# Bluesaab_RN52_v5_5-DPAK.net
KiCad netlist of a schematic drawn in EAGLE
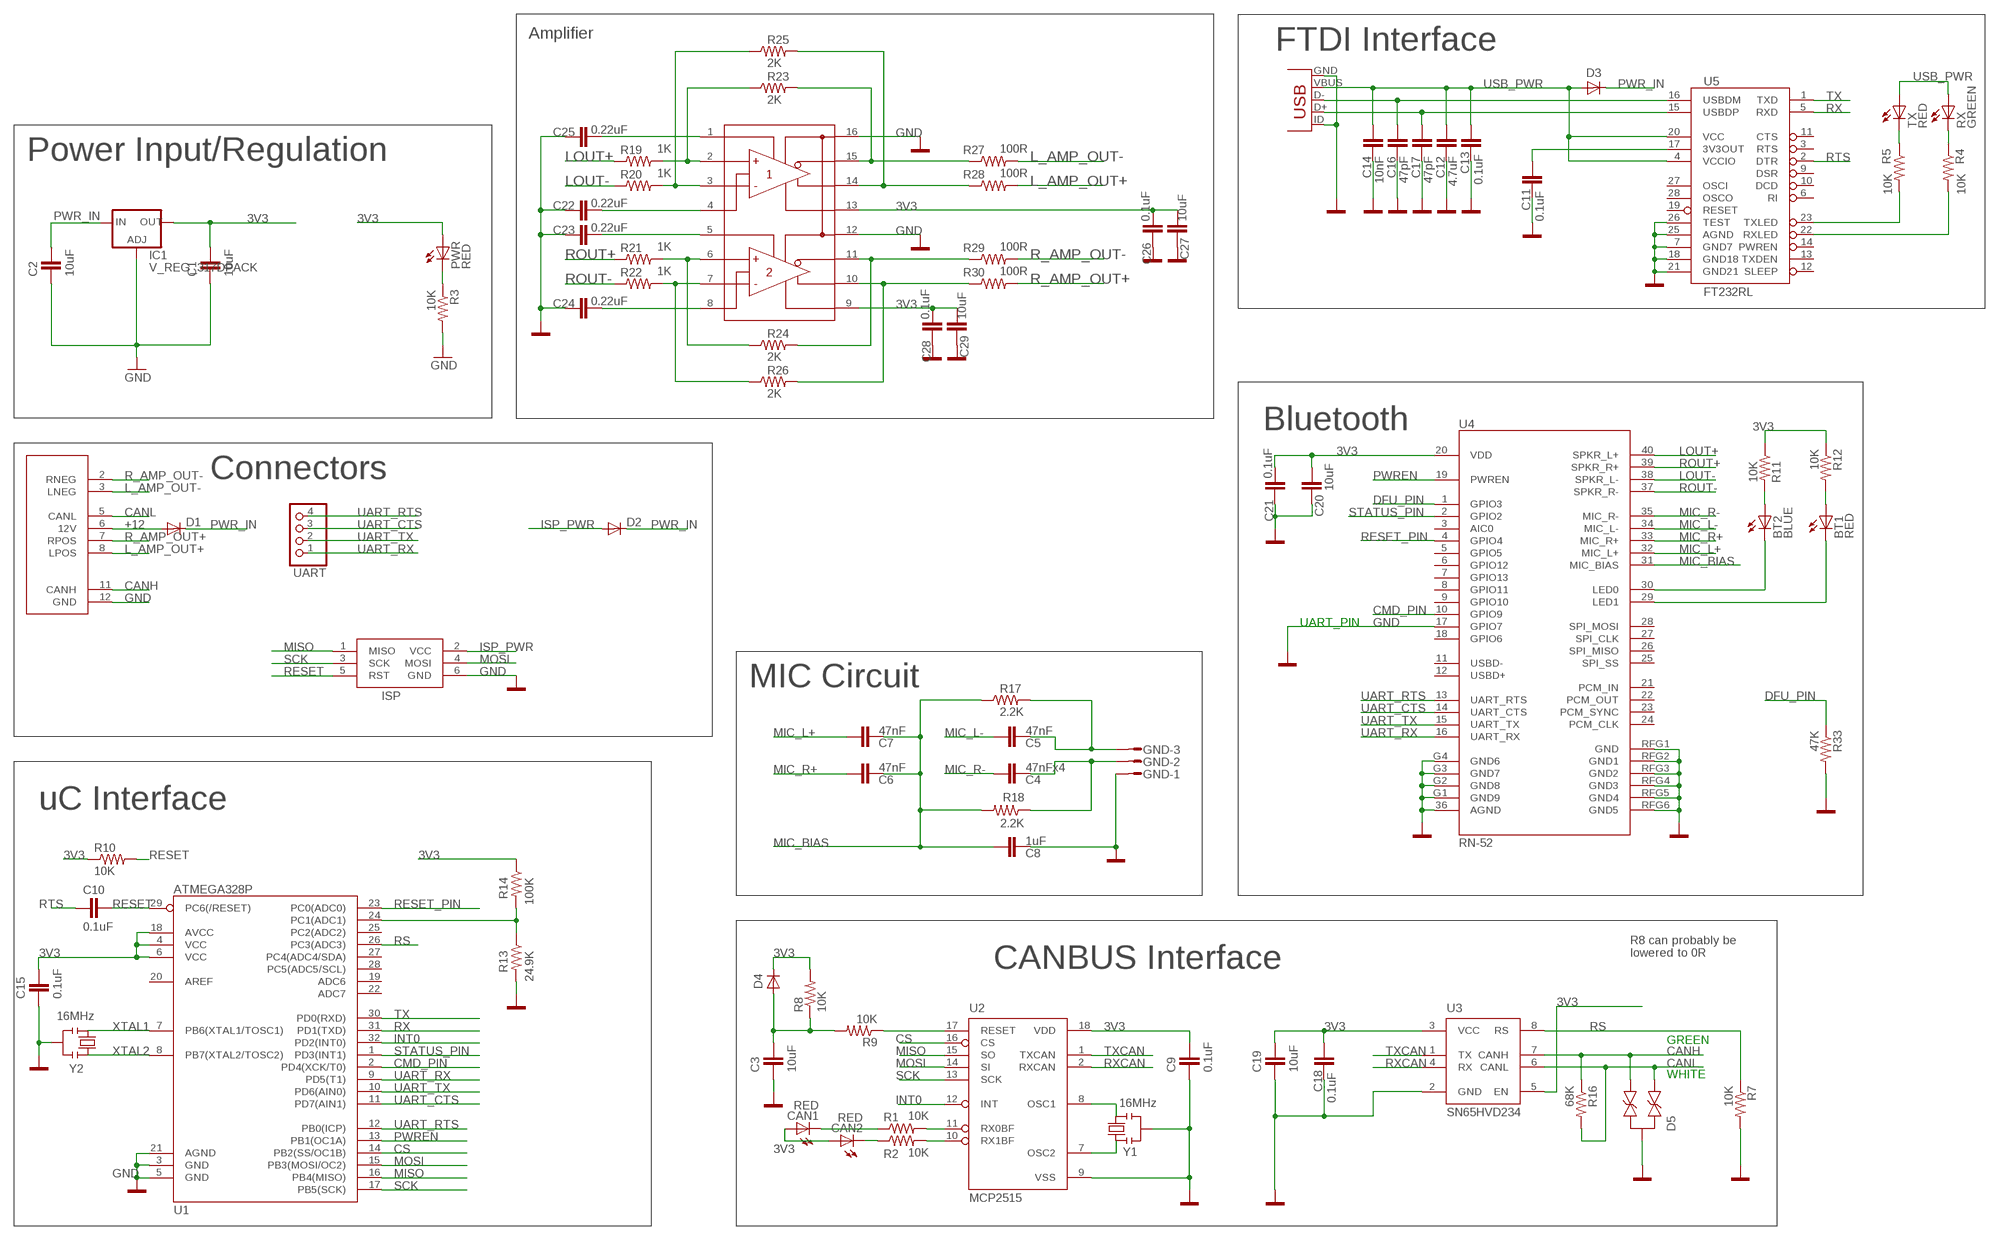
[diagram p0: schematic, sheet 1]

(export (version "E")
  (design (tool "Eeschema 10.0.6"))
  (components
    (comp (ref "BT1")
      (value "RED")
      (footprint "eagle-import:CHIPLED_0805")
      (libsource (lib "eagle-import") (part "LEDCHIPLED_0805"))
    )
    (comp (ref "BT2")
      (value "BLUE")
      (footprint "eagle-import:CHIPLED_0805")
      (libsource (lib "eagle-import") (part "LEDCHIPLED_0805"))
    )
    (comp (ref "C1")
      (value "10uF")
      (footprint "eagle-import:C0805K")
      (libsource (lib "eagle-import") (part "C-EUC0805K"))
    )
    (comp (ref "C2")
      (value "10uF")
      (footprint "eagle-import:C0805K")
      (libsource (lib "eagle-import") (part "C-EUC0805K"))
    )
    (comp (ref "C3")
      (value "10uF")
      (footprint "eagle-import:C0805K")
      (libsource (lib "eagle-import") (part "C-EUC0805K"))
    )
    (comp (ref "C4")
      (value "47nFx4")
      (footprint "eagle-import:C0805K")
      (libsource (lib "eagle-import") (part "C-EUC0805K"))
    )
    (comp (ref "C5")
      (value "47nF")
      (footprint "eagle-import:C0805K")
      (libsource (lib "eagle-import") (part "C-EUC0805K"))
    )
    (comp (ref "C6")
      (value "47nF")
      (footprint "eagle-import:C0805K")
      (libsource (lib "eagle-import") (part "C-EUC0805K"))
    )
    (comp (ref "C7")
      (value "47nF")
      (footprint "eagle-import:C0805K")
      (libsource (lib "eagle-import") (part "C-EUC0805K"))
    )
    (comp (ref "C8")
      (value "1uF")
      (footprint "eagle-import:C0805K")
      (libsource (lib "eagle-import") (part "C-EUC0805K"))
    )
    (comp (ref "C9")
      (value "0.1uF")
      (footprint "eagle-import:C0805K")
      (libsource (lib "eagle-import") (part "C-EUC0805K"))
    )
    (comp (ref "C10")
      (value "0.1uF")
      (footprint "eagle-import:C0805K")
      (libsource (lib "eagle-import") (part "C-EUC0805K"))
    )
    (comp (ref "C11")
      (value "0.1uF")
      (footprint "eagle-import:C0805K")
      (libsource (lib "eagle-import") (part "C-EUC0805K"))
    )
    (comp (ref "C12")
      (value "4.7uF")
      (footprint "eagle-import:C0805K")
      (libsource (lib "eagle-import") (part "C-EUC0805K"))
    )
    (comp (ref "C13")
      (value "0.1uF")
      (footprint "eagle-import:C0805K")
      (libsource (lib "eagle-import") (part "C-EUC0805K"))
    )
    (comp (ref "C14")
      (value "10nF")
      (footprint "eagle-import:C0805K")
      (libsource (lib "eagle-import") (part "C-EUC0805K"))
    )
    (comp (ref "C15")
      (value "0.1uF")
      (footprint "eagle-import:C0805K")
      (libsource (lib "eagle-import") (part "C-EUC0805K"))
    )
    (comp (ref "C16")
      (value "47pF")
      (footprint "eagle-import:C0805K")
      (libsource (lib "eagle-import") (part "C-EUC0805K"))
    )
    (comp (ref "C17")
      (value "47pF")
      (footprint "eagle-import:C0805K")
      (libsource (lib "eagle-import") (part "C-EUC0805K"))
    )
    (comp (ref "C18")
      (value "0.1uF")
      (footprint "eagle-import:C0805K")
      (libsource (lib "eagle-import") (part "C-EUC0805K"))
    )
    (comp (ref "C19")
      (value "10uF")
      (footprint "eagle-import:C0805K")
      (libsource (lib "eagle-import") (part "C-EUC0805K"))
    )
    (comp (ref "C20")
      (value "10uF")
      (footprint "eagle-import:C0805K")
      (libsource (lib "eagle-import") (part "C-EUC0805K"))
    )
    (comp (ref "C21")
      (value "0.1uF")
      (footprint "eagle-import:C0805K")
      (libsource (lib "eagle-import") (part "C-EUC0805K"))
    )
    (comp (ref "C22")
      (value "0.22uF")
      (footprint "eagle-import:C0805K")
      (libsource (lib "eagle-import") (part "C-EUC0805K"))
    )
    (comp (ref "C23")
      (value "0.22uF")
      (footprint "eagle-import:C0805K")
      (libsource (lib "eagle-import") (part "C-EUC0805K"))
    )
    (comp (ref "C24")
      (value "0.22uF")
      (footprint "eagle-import:C0805K")
      (libsource (lib "eagle-import") (part "C-EUC0805K"))
    )
    (comp (ref "C25")
      (value "0.22uF")
      (footprint "eagle-import:C0805K")
      (libsource (lib "eagle-import") (part "C-EUC0805K"))
    )
    (comp (ref "C26")
      (value "0.1uF")
      (footprint "eagle-import:C0805K")
      (libsource (lib "eagle-import") (part "C-EUC0805K"))
    )
    (comp (ref "C27")
      (value "10uF")
      (footprint "eagle-import:C0805K")
      (libsource (lib "eagle-import") (part "C-EUC0805K"))
    )
    (comp (ref "C28")
      (value "0.1uF")
      (footprint "eagle-import:C0805K")
      (libsource (lib "eagle-import") (part "C-EUC0805K"))
    )
    (comp (ref "C29")
      (value "10uF")
      (footprint "eagle-import:C0805K")
      (libsource (lib "eagle-import") (part "C-EUC0805K"))
    )
    (comp (ref "CAN1")
      (value "RED")
      (footprint "eagle-import:CHIPLED_0805")
      (libsource (lib "eagle-import") (part "LEDCHIPLED_0805"))
    )
    (comp (ref "CAN2")
      (value "RED")
      (footprint "eagle-import:CHIPLED_0805")
      (libsource (lib "eagle-import") (part "LEDCHIPLED_0805"))
    )
    (comp (ref "CDC_CONNECTOR")
      (value "827229-1")
      (footprint "eagle-import:827229-1")
      (libsource (lib "eagle-import") (part "827229-1"))
    )
    (comp (ref "D1")
      (value "DIODE-SCHOTTKY_")
      (footprint "eagle-import:SOD123")
      (libsource (lib "eagle-import") (part "DIODE-SOD123"))
    )
    (comp (ref "D2")
      (value "DIODE-SCHOTTKY_")
      (footprint "eagle-import:SOD123")
      (libsource (lib "eagle-import") (part "DIODE-SOD123"))
    )
    (comp (ref "D3")
      (value "DIODE-SCHOTTKY_")
      (footprint "eagle-import:SOD123")
      (libsource (lib "eagle-import") (part "DIODE-SOD123"))
    )
    (comp (ref "D4")
      (value "DIODE-SCHOTTKY_")
      (footprint "eagle-import:SOD123")
      (libsource (lib "eagle-import") (part "DIODE-SOD123"))
    )
    (comp (ref "D5")
      (value "DIODE-ARRAY")
      (footprint "eagle-import:SOT23")
      (libsource (lib "eagle-import") (part "DIODE-ARRAY"))
    )
    (comp (ref "GND")
      (value "S03P")
      (footprint "eagle-import:S03P")
      (libsource (lib "eagle-import") (part "S03P"))
    )
    (comp (ref "IC1")
      (value "V_REG_317DPACK")
      (footprint "eagle-import:V-REG_DPACK")
      (libsource (lib "eagle-import") (part "V_REG_317DPACK"))
    )
    (comp (ref "ISP")
      (value "AVRISP-6")
      (footprint "eagle-import:AVRISP")
      (libsource (lib "eagle-import") (part "AVRISP-6"))
    )
    (comp (ref "PWR")
      (value "RED")
      (footprint "eagle-import:CHIPLED_0805")
      (libsource (lib "eagle-import") (part "LEDCHIPLED_0805"))
    )
    (comp (ref "R1")
      (value "10K")
      (footprint "eagle-import:R0805")
      (libsource (lib "eagle-import") (part "R-US_R0805"))
    )
    (comp (ref "R2")
      (value "10K")
      (footprint "eagle-import:R0805")
      (libsource (lib "eagle-import") (part "R-US_R0805"))
    )
    (comp (ref "R3")
      (value "10K")
      (footprint "eagle-import:R0805")
      (libsource (lib "eagle-import") (part "R-US_R0805"))
    )
    (comp (ref "R4")
      (value "10K")
      (footprint "eagle-import:R0805")
      (libsource (lib "eagle-import") (part "R-US_R0805"))
    )
    (comp (ref "R5")
      (value "10K")
      (footprint "eagle-import:R0805")
      (libsource (lib "eagle-import") (part "R-US_R0805"))
    )
    (comp (ref "R7")
      (value "10K")
      (footprint "eagle-import:R0805")
      (libsource (lib "eagle-import") (part "R-US_R0805"))
    )
    (comp (ref "R8")
      (value "10K")
      (footprint "eagle-import:R0805")
      (libsource (lib "eagle-import") (part "R-US_R0805"))
    )
    (comp (ref "R9")
      (value "10K")
      (footprint "eagle-import:R0805")
      (libsource (lib "eagle-import") (part "R-US_R0805"))
    )
    (comp (ref "R10")
      (value "10K")
      (footprint "eagle-import:R0805")
      (libsource (lib "eagle-import") (part "R-US_R0805"))
    )
    (comp (ref "R11")
      (value "10K")
      (footprint "eagle-import:R0805")
      (libsource (lib "eagle-import") (part "R-US_R0805"))
    )
    (comp (ref "R12")
      (value "10K")
      (footprint "eagle-import:R0805")
      (libsource (lib "eagle-import") (part "R-US_R0805"))
    )
    (comp (ref "R13")
      (value "24.9K")
      (footprint "eagle-import:R0805")
      (libsource (lib "eagle-import") (part "R-US_R0805"))
    )
    (comp (ref "R14")
      (value "100K")
      (footprint "eagle-import:R0805")
      (libsource (lib "eagle-import") (part "R-US_R0805"))
    )
    (comp (ref "R16")
      (value "68K")
      (footprint "eagle-import:R0805")
      (libsource (lib "eagle-import") (part "R-US_R0805"))
    )
    (comp (ref "R17")
      (value "2.2K")
      (footprint "eagle-import:R0805")
      (libsource (lib "eagle-import") (part "R-US_R0805"))
    )
    (comp (ref "R18")
      (value "2.2K")
      (footprint "eagle-import:R0805")
      (libsource (lib "eagle-import") (part "R-US_R0805"))
    )
    (comp (ref "R19")
      (value "1K")
      (footprint "eagle-import:R0805")
      (libsource (lib "eagle-import") (part "R-US_R0805"))
    )
    (comp (ref "R20")
      (value "1K")
      (footprint "eagle-import:R0805")
      (libsource (lib "eagle-import") (part "R-US_R0805"))
    )
    (comp (ref "R21")
      (value "1K")
      (footprint "eagle-import:R0805")
      (libsource (lib "eagle-import") (part "R-US_R0805"))
    )
    (comp (ref "R22")
      (value "1K")
      (footprint "eagle-import:R0805")
      (libsource (lib "eagle-import") (part "R-US_R0805"))
    )
    (comp (ref "R23")
      (value "2K")
      (footprint "eagle-import:R0805")
      (libsource (lib "eagle-import") (part "R-US_R0805"))
    )
    (comp (ref "R24")
      (value "2K")
      (footprint "eagle-import:R0805")
      (libsource (lib "eagle-import") (part "R-US_R0805"))
    )
    (comp (ref "R25")
      (value "2K")
      (footprint "eagle-import:R0805")
      (libsource (lib "eagle-import") (part "R-US_R0805"))
    )
    (comp (ref "R26")
      (value "2K")
      (footprint "eagle-import:R0805")
      (libsource (lib "eagle-import") (part "R-US_R0805"))
    )
    (comp (ref "R27")
      (value "100R")
      (footprint "eagle-import:R0805")
      (libsource (lib "eagle-import") (part "R-US_R0805"))
    )
    (comp (ref "R28")
      (value "100R")
      (footprint "eagle-import:R0805")
      (libsource (lib "eagle-import") (part "R-US_R0805"))
    )
    (comp (ref "R29")
      (value "100R")
      (footprint "eagle-import:R0805")
      (libsource (lib "eagle-import") (part "R-US_R0805"))
    )
    (comp (ref "R30")
      (value "100R")
      (footprint "eagle-import:R0805")
      (libsource (lib "eagle-import") (part "R-US_R0805"))
    )
    (comp (ref "R33")
      (value "47K")
      (footprint "eagle-import:R0805")
      (libsource (lib "eagle-import") (part "R-US_R0805"))
    )
    (comp (ref "RX")
      (value "GREEN")
      (footprint "eagle-import:CHIPLED_0805")
      (libsource (lib "eagle-import") (part "LEDCHIPLED_0805"))
    )
    (comp (ref "TX")
      (value "RED")
      (footprint "eagle-import:CHIPLED_0805")
      (libsource (lib "eagle-import") (part "LEDCHIPLED_0805"))
    )
    (comp (ref "U1")
      (value "ATMEGA328P")
      (footprint "eagle-import:TQFP32-08")
      (libsource (lib "eagle-import") (part "ATMEGA328_SMT"))
    )
    (comp (ref "U2")
      (value "MCP2515")
      (footprint "eagle-import:SO18L")
      (libsource (lib "eagle-import") (part "MCP2515"))
    )
    (comp (ref "U3")
      (value "SN65HVD234")
      (footprint "eagle-import:SO8")
      (libsource (lib "eagle-import") (part "SN65HVD234"))
    )
    (comp (ref "U4")
      (value "RN-52")
      (footprint "eagle-import:RN-52")
      (libsource (lib "eagle-import") (part "BLUETOOTH-RN-52"))
    )
    (comp (ref "U5")
      (value "FT232RL")
      (footprint "eagle-import:SSOP28DB")
      (libsource (lib "eagle-import") (part "FT232RLSSOP"))
    )
    (comp (ref "U7")
      (value "THS4522")
      (footprint "eagle-import:TSSOP-16")
      (libsource (lib "eagle-import") (part "THS4522"))
    )
    (comp (ref "UART")
      (value "PINHD-1X4")
      (footprint "eagle-import:1X04")
      (libsource (lib "eagle-import") (part "PINHD-1X4"))
    )
    (comp (ref "UPLOAD")
      (value "USB-MB-H")
      (footprint "eagle-import:USB-MB-H")
      (libsource (lib "eagle-import") (part "USB-MB-H"))
    )
    (comp (ref "Y1")
      (value "16MHz")
      (footprint "eagle-import:RESONATOR-SMD")
      (libsource (lib "eagle-import") (part "RESONATORSMD"))
    )
    (comp (ref "Y2")
      (value "16MHz")
      (footprint "eagle-import:RESONATOR-SMD")
      (libsource (lib "eagle-import") (part "RESONATORSMD"))
    )
  )
  (nets
    (net (code "1") (name "/+12") (class "Default")
      (node (ref "CDC_CONNECTOR") (pin "6") (pinfunction "12V_6") (pintype "bidirectional"))
      (node (ref "D1") (pin "A") (pinfunction "A_A") (pintype "passive"))
    )
    (net (code "2") (name "/3V3") (class "Default")
      (node (ref "C1") (pin "2") (pinfunction "2_2") (pintype "passive"))
      (node (ref "C15") (pin "2") (pinfunction "2_2") (pintype "passive"))
      (node (ref "C18") (pin "1") (pinfunction "1_1") (pintype "passive"))
      (node (ref "C19") (pin "2") (pinfunction "2_2") (pintype "passive"))
      (node (ref "C20") (pin "1") (pinfunction "1_1") (pintype "passive"))
      (node (ref "C21") (pin "2") (pinfunction "2_2") (pintype "passive"))
      (node (ref "C26") (pin "2") (pinfunction "2_2") (pintype "passive"))
      (node (ref "C27") (pin "1") (pinfunction "1_1") (pintype "passive"))
      (node (ref "C28") (pin "2") (pinfunction "2_2") (pintype "passive"))
      (node (ref "C29") (pin "1") (pinfunction "1_1") (pintype "passive"))
      (node (ref "C9") (pin "2") (pinfunction "2_2") (pintype "passive"))
      (node (ref "CAN1") (pin "A") (pinfunction "A_A") (pintype "passive"))
      (node (ref "CAN2") (pin "A") (pinfunction "A_A") (pintype "passive"))
      (node (ref "D4") (pin "C") (pinfunction "C_C") (pintype "passive"))
      (node (ref "IC1") (pin "4") (pinfunction "OUT_4") (pintype "output"))
      (node (ref "PWR") (pin "A") (pinfunction "A_A") (pintype "passive"))
      (node (ref "R10") (pin "1") (pinfunction "1_1") (pintype "passive"))
      (node (ref "R11") (pin "1") (pinfunction "1_1") (pintype "passive"))
      (node (ref "R12") (pin "1") (pinfunction "1_1") (pintype "passive"))
      (node (ref "R14") (pin "1") (pinfunction "1_1") (pintype "passive"))
      (node (ref "R8") (pin "2") (pinfunction "2_2") (pintype "passive"))
      (node (ref "U1") (pin "18") (pinfunction "AVCC_18") (pintype "bidirectional"))
      (node (ref "U1") (pin "4") (pinfunction "VCC_4") (pintype "bidirectional"))
      (node (ref "U1") (pin "6") (pinfunction "VCC_6") (pintype "bidirectional"))
      (node (ref "U2") (pin "18") (pinfunction "VDD_18") (pintype "power_in"))
      (node (ref "U3") (pin "3") (pinfunction "VCC_3") (pintype "power_in"))
      (node (ref "U3") (pin "5") (pinfunction "EN_5") (pintype "bidirectional"))
      (node (ref "U4") (pin "20") (pinfunction "VDD_20") (pintype "bidirectional"))
      (node (ref "U7") (pin "13") (pinfunction "13.VS+1_13") (pintype "power_in"))
      (node (ref "U7") (pin "9") (pinfunction "9.VS+2_9") (pintype "power_in"))
    )
    (net (code "3") (name "/CANH") (class "Default")
      (node (ref "CDC_CONNECTOR") (pin "11") (pinfunction "CANH_11") (pintype "bidirectional"))
      (node (ref "D5") (pin "2") (pinfunction "2_2") (pintype "bidirectional"))
      (node (ref "R16") (pin "1") (pinfunction "1_1") (pintype "passive"))
      (node (ref "U3") (pin "7") (pinfunction "CANH_7") (pintype "bidirectional"))
    )
    (net (code "4") (name "/CANL") (class "Default")
      (node (ref "CDC_CONNECTOR") (pin "5") (pinfunction "CANL_5") (pintype "bidirectional"))
      (node (ref "D5") (pin "1") (pinfunction "1_1") (pintype "bidirectional"))
      (node (ref "R16") (pin "2") (pinfunction "2_2") (pintype "passive"))
      (node (ref "U3") (pin "6") (pinfunction "CANL_6") (pintype "bidirectional"))
    )
    (net (code "5") (name "/CMD_PIN") (class "Default")
      (node (ref "U1") (pin "2") (pinfunction "PD4(XCK/T0)_2") (pintype "bidirectional"))
      (node (ref "U4") (pin "10") (pinfunction "GPIO9_10") (pintype "bidirectional"))
    )
    (net (code "6") (name "/CS") (class "Default")
      (node (ref "U1") (pin "14") (pinfunction "PB2(SS/OC1B)_14") (pintype "bidirectional"))
      (node (ref "U2") (pin "16") (pinfunction "CS_16") (pintype "input"))
    )
    (net (code "7") (name "/DFU_PIN") (class "Default")
      (node (ref "R33") (pin "1") (pinfunction "1_1") (pintype "passive"))
      (node (ref "U4") (pin "1") (pinfunction "GPIO3_1") (pintype "bidirectional"))
    )
    (net (code "8") (name "/INT0") (class "Default")
      (node (ref "U1") (pin "32") (pinfunction "PD2(INT0)_32") (pintype "bidirectional"))
      (node (ref "U2") (pin "12") (pinfunction "INT_12") (pintype "output"))
    )
    (net (code "9") (name "/ISP_PWR") (class "Default")
      (node (ref "D2") (pin "A") (pinfunction "A_A") (pintype "passive"))
      (node (ref "ISP") (pin "2") (pinfunction "VCC_2") (pintype "power_in"))
    )
    (net (code "10") (name "/LOUT+") (class "Default")
      (node (ref "R19") (pin "1") (pinfunction "1_1") (pintype "passive"))
      (node (ref "U4") (pin "40") (pinfunction "SPKR_L+_40") (pintype "bidirectional"))
    )
    (net (code "11") (name "/LOUT-") (class "Default")
      (node (ref "R20") (pin "1") (pinfunction "1_1") (pintype "passive"))
      (node (ref "U4") (pin "38") (pinfunction "SPKR_L-_38") (pintype "bidirectional"))
    )
    (net (code "12") (name "/L_AMP_OUT+") (class "Default")
      (node (ref "CDC_CONNECTOR") (pin "8") (pinfunction "LPOS_8") (pintype "bidirectional"))
      (node (ref "R28") (pin "2") (pinfunction "2_2") (pintype "passive"))
    )
    (net (code "13") (name "/L_AMP_OUT-") (class "Default")
      (node (ref "CDC_CONNECTOR") (pin "3") (pinfunction "LNEG_3") (pintype "bidirectional"))
      (node (ref "R27") (pin "2") (pinfunction "2_2") (pintype "passive"))
    )
    (net (code "14") (name "/MIC_BIAS") (class "Default")
      (node (ref "C6") (pin "1") (pinfunction "1_1") (pintype "passive"))
      (node (ref "C7") (pin "1") (pinfunction "1_1") (pintype "passive"))
      (node (ref "C8") (pin "2") (pinfunction "2_2") (pintype "passive"))
      (node (ref "R17") (pin "1") (pinfunction "1_1") (pintype "passive"))
      (node (ref "R18") (pin "2") (pinfunction "2_2") (pintype "passive"))
      (node (ref "U4") (pin "31") (pinfunction "MIC_BIAS_31") (pintype "bidirectional"))
    )
    (net (code "15") (name "/MIC_L+") (class "Default")
      (node (ref "C7") (pin "2") (pinfunction "2_2") (pintype "passive"))
      (node (ref "U4") (pin "32") (pinfunction "MIC_L+_32") (pintype "bidirectional"))
    )
    (net (code "16") (name "/MIC_L-") (class "Default")
      (node (ref "C5") (pin "1") (pinfunction "1_1") (pintype "passive"))
      (node (ref "U4") (pin "34") (pinfunction "MIC_L-_34") (pintype "bidirectional"))
    )
    (net (code "17") (name "/MIC_R+") (class "Default")
      (node (ref "C6") (pin "2") (pinfunction "2_2") (pintype "passive"))
      (node (ref "U4") (pin "33") (pinfunction "MIC_R+_33") (pintype "bidirectional"))
    )
    (net (code "18") (name "/MIC_R-") (class "Default")
      (node (ref "C4") (pin "1") (pinfunction "1_1") (pintype "passive"))
      (node (ref "U4") (pin "35") (pinfunction "MIC_R-_35") (pintype "bidirectional"))
    )
    (net (code "19") (name "/MISO") (class "Default")
      (node (ref "ISP") (pin "1") (pinfunction "MISO_1") (pintype "input"))
      (node (ref "U1") (pin "16") (pinfunction "PB4(MISO)_16") (pintype "bidirectional"))
      (node (ref "U2") (pin "15") (pinfunction "SO_15") (pintype "output"))
    )
    (net (code "20") (name "/MOSI") (class "Default")
      (node (ref "ISP") (pin "4") (pinfunction "MOSI_4") (pintype "output"))
      (node (ref "U1") (pin "15") (pinfunction "PB3(MOSI/OC2)_15") (pintype "bidirectional"))
      (node (ref "U2") (pin "14") (pinfunction "SI_14") (pintype "input"))
    )
    (net (code "21") (name "/PWREN") (class "Default")
      (node (ref "U1") (pin "13") (pinfunction "PB1(OC1A)_13") (pintype "bidirectional"))
      (node (ref "U4") (pin "19") (pinfunction "PWREN_19") (pintype "bidirectional"))
    )
    (net (code "22") (name "/PWR_IN") (class "Default")
      (node (ref "C2") (pin "2") (pinfunction "2_2") (pintype "passive"))
      (node (ref "D1") (pin "C") (pinfunction "C_C") (pintype "passive"))
      (node (ref "D2") (pin "C") (pinfunction "C_C") (pintype "passive"))
      (node (ref "D3") (pin "C") (pinfunction "C_C") (pintype "passive"))
      (node (ref "IC1") (pin "3") (pinfunction "IN_3") (pintype "input"))
    )
    (net (code "23") (name "/RESET") (class "Default")
      (node (ref "C10") (pin "2") (pinfunction "2_2") (pintype "passive"))
      (node (ref "ISP") (pin "5") (pinfunction "RST_5") (pintype "output"))
      (node (ref "R10") (pin "2") (pinfunction "2_2") (pintype "passive"))
      (node (ref "U1") (pin "29") (pinfunction "PC6(/RESET)_29") (pintype "bidirectional"))
    )
    (net (code "24") (name "/RESET_PIN") (class "Default")
      (node (ref "U1") (pin "23") (pinfunction "PC0(ADC0)_23") (pintype "bidirectional"))
      (node (ref "U4") (pin "4") (pinfunction "GPIO4_4") (pintype "bidirectional"))
    )
    (net (code "25") (name "/ROUT+") (class "Default")
      (node (ref "R21") (pin "1") (pinfunction "1_1") (pintype "passive"))
      (node (ref "U4") (pin "39") (pinfunction "SPKR_R+_39") (pintype "bidirectional"))
    )
    (net (code "26") (name "/ROUT-") (class "Default")
      (node (ref "R22") (pin "1") (pinfunction "1_1") (pintype "passive"))
      (node (ref "U4") (pin "37") (pinfunction "SPKR_R-_37") (pintype "bidirectional"))
    )
    (net (code "27") (name "/RS") (class "Default")
      (node (ref "R7") (pin "1") (pinfunction "1_1") (pintype "passive"))
      (node (ref "U1") (pin "26") (pinfunction "PC3(ADC3)_26") (pintype "bidirectional"))
      (node (ref "U3") (pin "8") (pinfunction "RS_8") (pintype "bidirectional"))
    )
    (net (code "28") (name "/RTS") (class "Default")
      (node (ref "C10") (pin "1") (pinfunction "1_1") (pintype "passive"))
      (node (ref "U5") (pin "2") (pinfunction "DTR_2") (pintype "output"))
    )
    (net (code "29") (name "/RX") (class "Default")
      (node (ref "U1") (pin "31") (pinfunction "PD1(TXD)_31") (pintype "bidirectional"))
      (node (ref "U5") (pin "5") (pinfunction "RXD_5") (pintype "input"))
    )
    (net (code "30") (name "/RXCAN") (class "Default")
      (node (ref "U2") (pin "2") (pinfunction "RXCAN_2") (pintype "input"))
      (node (ref "U3") (pin "4") (pinfunction "RX_4") (pintype "output"))
    )
    (net (code "31") (name "/R_AMP_OUT+") (class "Default")
      (node (ref "CDC_CONNECTOR") (pin "7") (pinfunction "RPOS_7") (pintype "bidirectional"))
      (node (ref "R30") (pin "2") (pinfunction "2_2") (pintype "passive"))
    )
    (net (code "32") (name "/R_AMP_OUT-") (class "Default")
      (node (ref "CDC_CONNECTOR") (pin "2") (pinfunction "RNEG_2") (pintype "bidirectional"))
      (node (ref "R29") (pin "2") (pinfunction "2_2") (pintype "passive"))
    )
    (net (code "33") (name "/SCK") (class "Default")
      (node (ref "ISP") (pin "3") (pinfunction "SCK_3") (pintype "output"))
      (node (ref "U1") (pin "17") (pinfunction "PB5(SCK)_17") (pintype "bidirectional"))
      (node (ref "U2") (pin "13") (pinfunction "SCK_13") (pintype "input"))
    )
    (net (code "34") (name "/STATUS_PIN") (class "Default")
      (node (ref "U1") (pin "1") (pinfunction "PD3(INT1)_1") (pintype "bidirectional"))
      (node (ref "U4") (pin "2") (pinfunction "GPIO2_2") (pintype "bidirectional"))
    )
    (net (code "35") (name "/TX") (class "Default")
      (node (ref "U1") (pin "30") (pinfunction "PD0(RXD)_30") (pintype "bidirectional"))
      (node (ref "U5") (pin "1") (pinfunction "TXD_1") (pintype "output"))
    )
    (net (code "36") (name "/TXCAN") (class "Default")
      (node (ref "U2") (pin "1") (pinfunction "TXCAN_1") (pintype "output"))
      (node (ref "U3") (pin "1") (pinfunction "TX_1") (pintype "input"))
    )
    (net (code "37") (name "/UART_CTS") (class "Default")
      (node (ref "U1") (pin "11") (pinfunction "PD7(AIN1)_11") (pintype "bidirectional"))
      (node (ref "U4") (pin "14") (pinfunction "UART_CTS_14") (pintype "bidirectional"))
      (node (ref "UART") (pin "3") (pinfunction "3_3") (pintype "passive"))
    )
    (net (code "38") (name "/UART_RTS") (class "Default")
      (node (ref "U1") (pin "12") (pinfunction "PB0(ICP)_12") (pintype "bidirectional"))
      (node (ref "U4") (pin "13") (pinfunction "UART_RTS_13") (pintype "bidirectional"))
      (node (ref "UART") (pin "4") (pinfunction "4_4") (pintype "passive"))
    )
    (net (code "39") (name "/UART_RX") (class "Default")
      (node (ref "U1") (pin "9") (pinfunction "PD5(T1)_9") (pintype "bidirectional"))
      (node (ref "U4") (pin "16") (pinfunction "UART_RX_16") (pintype "bidirectional"))
      (node (ref "UART") (pin "1") (pinfunction "1_1") (pintype "passive"))
    )
    (net (code "40") (name "/UART_TX") (class "Default")
      (node (ref "U1") (pin "10") (pinfunction "PD6(AIN0)_10") (pintype "bidirectional"))
      (node (ref "U4") (pin "15") (pinfunction "UART_TX_15") (pintype "bidirectional"))
      (node (ref "UART") (pin "2") (pinfunction "2_2") (pintype "passive"))
    )
    (net (code "41") (name "/USB_PWR") (class "Default")
      (node (ref "C12") (pin "2") (pinfunction "2_2") (pintype "passive"))
      (node (ref "C13") (pin "1") (pinfunction "1_1") (pintype "passive"))
      (node (ref "C14") (pin "2") (pinfunction "2_2") (pintype "passive"))
      (node (ref "D3") (pin "A") (pinfunction "A_A") (pintype "passive"))
      (node (ref "RX") (pin "A") (pinfunction "A_A") (pintype "passive"))
      (node (ref "TX") (pin "A") (pinfunction "A_A") (pintype "passive"))
      (node (ref "U5") (pin "20") (pinfunction "VCC_20") (pintype "power_in"))
      (node (ref "U5") (pin "4") (pinfunction "VCCIO_4") (pintype "power_in"))
      (node (ref "UPLOAD") (pin "VBUS") (pinfunction "VBUS_VBUS") (pintype "bidirectional"))
    )
    (net (code "42") (name "/XTAL1") (class "Default")
      (node (ref "U1") (pin "7") (pinfunction "PB6(XTAL1/TOSC1)_7") (pintype "bidirectional"))
      (node (ref "Y2") (pin "1") (pinfunction "1_1") (pintype "bidirectional"))
    )
    (net (code "43") (name "/XTAL2") (class "Default")
      (node (ref "U1") (pin "8") (pinfunction "PB7(XTAL2/TOSC2)_8") (pintype "bidirectional"))
      (node (ref "Y2") (pin "3") (pinfunction "3_3") (pintype "bidirectional"))
    )
    (net (code "44") (name "GND") (class "Default")
      (node (ref "C1") (pin "1") (pinfunction "1_1") (pintype "passive"))
      (node (ref "C11") (pin "2") (pinfunction "2_2") (pintype "passive"))
      (node (ref "C12") (pin "1") (pinfunction "1_1") (pintype "passive"))
      (node (ref "C13") (pin "2") (pinfunction "2_2") (pintype "passive"))
      (node (ref "C14") (pin "1") (pinfunction "1_1") (pintype "passive"))
      (node (ref "C15") (pin "1") (pinfunction "1_1") (pintype "passive"))
      (node (ref "C16") (pin "1") (pinfunction "1_1") (pintype "passive"))
      (node (ref "C17") (pin "1") (pinfunction "1_1") (pintype "passive"))
      (node (ref "C18") (pin "2") (pinfunction "2_2") (pintype "passive"))
      (node (ref "C19") (pin "1") (pinfunction "1_1") (pintype "passive"))
      (node (ref "C2") (pin "1") (pinfunction "1_1") (pintype "passive"))
      (node (ref "C20") (pin "2") (pinfunction "2_2") (pintype "passive"))
      (node (ref "C21") (pin "1") (pinfunction "1_1") (pintype "passive"))
      (node (ref "C22") (pin "2") (pinfunction "2_2") (pintype "passive"))
      (node (ref "C23") (pin "2") (pinfunction "2_2") (pintype "passive"))
      (node (ref "C24") (pin "2") (pinfunction "2_2") (pintype "passive"))
      (node (ref "C25") (pin "2") (pinfunction "2_2") (pintype "passive"))
      (node (ref "C26") (pin "1") (pinfunction "1_1") (pintype "passive"))
      (node (ref "C27") (pin "2") (pinfunction "2_2") (pintype "passive"))
      (node (ref "C28") (pin "1") (pinfunction "1_1") (pintype "passive"))
      (node (ref "C29") (pin "2") (pinfunction "2_2") (pintype "passive"))
      (node (ref "C3") (pin "1") (pinfunction "1_1") (pintype "passive"))
      (node (ref "C8") (pin "1") (pinfunction "1_1") (pintype "passive"))
      (node (ref "C9") (pin "1") (pinfunction "1_1") (pintype "passive"))
      (node (ref "CDC_CONNECTOR") (pin "12") (pinfunction "GND_12") (pintype "bidirectional"))
      (node (ref "D5") (pin "3") (pinfunction "3_3") (pintype "bidirectional"))
      (node (ref "GND") (pin "1") (pinfunction "S_1") (pintype "passive"))
      (node (ref "IC1") (pin "1") (pinfunction "ADJ_1") (pintype "input"))
      (node (ref "ISP") (pin "6") (pinfunction "GND_6") (pintype "power_in"))
      (node (ref "R13") (pin "2") (pinfunction "2_2") (pintype "passive"))
      (node (ref "R3") (pin "2") (pinfunction "2_2") (pintype "passive"))
      (node (ref "R33") (pin "2") (pinfunction "2_2") (pintype "passive"))
      (node (ref "R7") (pin "2") (pinfunction "2_2") (pintype "passive"))
      (node (ref "U1") (pin "21") (pinfunction "AGND_21") (pintype "bidirectional"))
      (node (ref "U1") (pin "3") (pinfunction "GND_3") (pintype "bidirectional"))
      (node (ref "U1") (pin "5") (pinfunction "GND_5") (pintype "bidirectional"))
      (node (ref "U2") (pin "9") (pinfunction "VSS_9") (pintype "power_in"))
      (node (ref "U3") (pin "2") (pinfunction "GND_2") (pintype "power_in"))
      (node (ref "U4") (pin "17") (pinfunction "GPIO7_17") (pintype "bidirectional"))
      (node (ref "U4") (pin "36") (pinfunction "AGND_36") (pintype "bidirectional"))
      (node (ref "U4") (pin "G1") (pinfunction "GND9_G1") (pintype "bidirectional"))
      (node (ref "U4") (pin "G2") (pinfunction "GND8_G2") (pintype "bidirectional"))
      (node (ref "U4") (pin "G3") (pinfunction "GND7_G3") (pintype "bidirectional"))
      (node (ref "U4") (pin "G4") (pinfunction "GND6_G4") (pintype "bidirectional"))
      (node (ref "U4") (pin "RFG1") (pinfunction "GND_RFG1") (pintype "bidirectional"))
      (node (ref "U4") (pin "RFG2") (pinfunction "GND1_RFG2") (pintype "bidirectional"))
      (node (ref "U4") (pin "RFG3") (pinfunction "GND2_RFG3") (pintype "bidirectional"))
      (node (ref "U4") (pin "RFG4") (pinfunction "GND3_RFG4") (pintype "bidirectional"))
      (node (ref "U4") (pin "RFG5") (pinfunction "GND4_RFG5") (pintype "bidirectional"))
      (node (ref "U4") (pin "RFG6") (pinfunction "GND5_RFG6") (pintype "bidirectional"))
      (node (ref "U5") (pin "18") (pinfunction "GND18_18") (pintype "power_in"))
      (node (ref "U5") (pin "21") (pinfunction "GND21_21") (pintype "power_in"))
      (node (ref "U5") (pin "25") (pinfunction "AGND_25") (pintype "power_in"))
      (node (ref "U5") (pin "26") (pinfunction "TEST_26") (pintype "input"))
      (node (ref "U5") (pin "7") (pinfunction "GND7_7") (pintype "power_in"))
      (node (ref "U7") (pin "12") (pinfunction "12.VS-_12") (pintype "power_in"))
      (node (ref "U7") (pin "16") (pinfunction "16.VS-_16") (pintype "power_in"))
      (node (ref "UPLOAD") (pin "GND") (pinfunction "GND_GND") (pintype "bidirectional"))
      (node (ref "UPLOAD") (pin "ID") (pinfunction "ID_ID") (pintype "bidirectional"))
      (node (ref "Y1") (pin "2") (pinfunction "2_2") (pintype "power_in"))
      (node (ref "Y2") (pin "2") (pinfunction "2_2") (pintype "power_in"))
    )
    (net (code "45") (name "Net-(BT1-PadA)") (class "Default")
      (node (ref "BT1") (pin "A") (pinfunction "A_A") (pintype "passive"))
      (node (ref "R12") (pin "2") (pinfunction "2_2") (pintype "passive"))
    )
    (net (code "46") (name "Net-(BT2-PadA)") (class "Default")
      (node (ref "BT2") (pin "A") (pinfunction "A_A") (pintype "passive"))
      (node (ref "R11") (pin "2") (pinfunction "2_2") (pintype "passive"))
    )
    (net (code "47") (name "Net-(C3-Pad2)") (class "Default")
      (node (ref "C3") (pin "2") (pinfunction "2_2") (pintype "passive"))
      (node (ref "D4") (pin "A") (pinfunction "A_A") (pintype "passive"))
      (node (ref "R8") (pin "1") (pinfunction "1_1") (pintype "passive"))
      (node (ref "R9") (pin "2") (pinfunction "2_2") (pintype "passive"))
    )
    (net (code "48") (name "Net-(CAN1-PadC)") (class "Default")
      (node (ref "CAN1") (pin "C") (pinfunction "C_C") (pintype "passive"))
      (node (ref "R1") (pin "1") (pinfunction "1_1") (pintype "passive"))
    )
    (net (code "49") (name "Net-(CAN2-PadC)") (class "Default")
      (node (ref "CAN2") (pin "C") (pinfunction "C_C") (pintype "passive"))
      (node (ref "R2") (pin "1") (pinfunction "1_1") (pintype "passive"))
    )
    (net (code "50") (name "Net-(GNDB-S)") (class "Default")
      (node (ref "C4") (pin "2") (pinfunction "2_2") (pintype "passive"))
      (node (ref "GND") (pin "2") (pinfunction "S_2") (pintype "passive"))
      (node (ref "R18") (pin "1") (pinfunction "1_1") (pintype "passive"))
    )
    (net (code "51") (name "Net-(GNDC-S)") (class "Default")
      (node (ref "C5") (pin "2") (pinfunction "2_2") (pintype "passive"))
      (node (ref "GND") (pin "3") (pinfunction "S_3") (pintype "passive"))
      (node (ref "R17") (pin "2") (pinfunction "2_2") (pintype "passive"))
    )
    (net (code "52") (name "Net-(PWR-PadC)") (class "Default")
      (node (ref "PWR") (pin "C") (pinfunction "C_C") (pintype "passive"))
      (node (ref "R3") (pin "1") (pinfunction "1_1") (pintype "passive"))
    )
    (net (code "53") (name "Net-(R4-Pad1)") (class "Default")
      (node (ref "R4") (pin "1") (pinfunction "1_1") (pintype "passive"))
      (node (ref "RX") (pin "C") (pinfunction "C_C") (pintype "passive"))
    )
    (net (code "54") (name "Net-(R5-Pad1)") (class "Default")
      (node (ref "R5") (pin "1") (pinfunction "1_1") (pintype "passive"))
      (node (ref "TX") (pin "C") (pinfunction "C_C") (pintype "passive"))
    )
    (net (code "55") (name "Net-(U1-PC1(ADC1))") (class "Default")
      (node (ref "R13") (pin "1") (pinfunction "1_1") (pintype "passive"))
      (node (ref "R14") (pin "2") (pinfunction "2_2") (pintype "passive"))
      (node (ref "U1") (pin "24") (pinfunction "PC1(ADC1)_24") (pintype "bidirectional"))
    )
    (net (code "56") (name "Net-(U2-OSC1)") (class "Default")
      (node (ref "U2") (pin "8") (pinfunction "OSC1_8") (pintype "input"))
      (node (ref "Y1") (pin "3") (pinfunction "3_3") (pintype "bidirectional"))
    )
    (net (code "57") (name "Net-(U2-OSC2)") (class "Default")
      (node (ref "U2") (pin "7") (pinfunction "OSC2_7") (pintype "output"))
      (node (ref "Y1") (pin "1") (pinfunction "1_1") (pintype "bidirectional"))
    )
    (net (code "58") (name "Net-(U2-RESET)") (class "Default")
      (node (ref "R9") (pin "1") (pinfunction "1_1") (pintype "passive"))
      (node (ref "U2") (pin "17") (pinfunction "RESET_17") (pintype "bidirectional"))
    )
    (net (code "59") (name "Net-(U2-RX0BF)") (class "Default")
      (node (ref "R1") (pin "2") (pinfunction "2_2") (pintype "passive"))
      (node (ref "U2") (pin "11") (pinfunction "RX0BF_11") (pintype "output"))
    )
    (net (code "60") (name "Net-(U2-RX1BF)") (class "Default")
      (node (ref "R2") (pin "2") (pinfunction "2_2") (pintype "passive"))
      (node (ref "U2") (pin "10") (pinfunction "RX1BF_10") (pintype "output"))
    )
    (net (code "61") (name "Net-(U4-LED0)") (class "Default")
      (node (ref "BT2") (pin "C") (pinfunction "C_C") (pintype "passive"))
      (node (ref "U4") (pin "30") (pinfunction "LED0_30") (pintype "bidirectional"))
    )
    (net (code "62") (name "Net-(U4-LED1)") (class "Default")
      (node (ref "BT1") (pin "C") (pinfunction "C_C") (pintype "passive"))
      (node (ref "U4") (pin "29") (pinfunction "LED1_29") (pintype "bidirectional"))
    )
    (net (code "63") (name "Net-(U5-3V3OUT)") (class "Default")
      (node (ref "C11") (pin "1") (pinfunction "1_1") (pintype "passive"))
      (node (ref "U5") (pin "17") (pinfunction "3V3OUT_17") (pintype "output"))
    )
    (net (code "64") (name "Net-(U5-RXLED)") (class "Default")
      (node (ref "R4") (pin "2") (pinfunction "2_2") (pintype "passive"))
      (node (ref "U5") (pin "22") (pinfunction "RXLED_22") (pintype "input"))
    )
    (net (code "65") (name "Net-(U5-TXLED)") (class "Default")
      (node (ref "R5") (pin "2") (pinfunction "2_2") (pintype "passive"))
      (node (ref "U5") (pin "23") (pinfunction "TXLED_23") (pintype "input"))
    )
    (net (code "66") (name "Net-(U5-USBDM)") (class "Default")
      (node (ref "C16") (pin "2") (pinfunction "2_2") (pintype "passive"))
      (node (ref "U5") (pin "16") (pinfunction "USBDM_16") (pintype "bidirectional"))
      (node (ref "UPLOAD") (pin "D-") (pinfunction "D-_D-") (pintype "bidirectional"))
    )
    (net (code "67") (name "Net-(U5-USBDP)") (class "Default")
      (node (ref "C17") (pin "2") (pinfunction "2_2") (pintype "passive"))
      (node (ref "U5") (pin "15") (pinfunction "USBDP_15") (pintype "bidirectional"))
      (node (ref "UPLOAD") (pin "D+") (pinfunction "D+_D+") (pintype "bidirectional"))
    )
    (net (code "68") (name "Net-(U7-1.PD1)") (class "Default")
      (node (ref "C25") (pin "1") (pinfunction "1_1") (pintype "passive"))
      (node (ref "U7") (pin "1") (pinfunction "1.PD1_1") (pintype "bidirectional"))
    )
    (net (code "69") (name "Net-(U7-2.VIN1+)") (class "Default")
      (node (ref "R19") (pin "2") (pinfunction "2_2") (pintype "passive"))
      (node (ref "R23") (pin "1") (pinfunction "1_1") (pintype "passive"))
      (node (ref "U7") (pin "2") (pinfunction "2.VIN1+_2") (pintype "input"))
    )
    (net (code "70") (name "Net-(U7-3.VIN1-)") (class "Default")
      (node (ref "R20") (pin "2") (pinfunction "2_2") (pintype "passive"))
      (node (ref "R25") (pin "1") (pinfunction "1_1") (pintype "passive"))
      (node (ref "U7") (pin "3") (pinfunction "3.VIN1-_3") (pintype "input"))
    )
    (net (code "71") (name "Net-(U7-4.OCM1)") (class "Default")
      (node (ref "C22") (pin "1") (pinfunction "1_1") (pintype "passive"))
      (node (ref "U7") (pin "4") (pinfunction "4.OCM1_4") (pintype "bidirectional"))
    )
    (net (code "72") (name "Net-(U7-5.PD2)") (class "Default")
      (node (ref "C23") (pin "1") (pinfunction "1_1") (pintype "passive"))
      (node (ref "U7") (pin "5") (pinfunction "5.PD2_5") (pintype "bidirectional"))
    )
    (net (code "73") (name "Net-(U7-6.IN2+)") (class "Default")
      (node (ref "R21") (pin "2") (pinfunction "2_2") (pintype "passive"))
      (node (ref "R24") (pin "1") (pinfunction "1_1") (pintype "passive"))
      (node (ref "U7") (pin "6") (pinfunction "6.IN2+_6") (pintype "input"))
    )
    (net (code "74") (name "Net-(U7-7.IN2-)") (class "Default")
      (node (ref "R22") (pin "2") (pinfunction "2_2") (pintype "passive"))
      (node (ref "R26") (pin "1") (pinfunction "1_1") (pintype "passive"))
      (node (ref "U7") (pin "7") (pinfunction "7.IN2-_7") (pintype "input"))
    )
    (net (code "75") (name "Net-(U7-8.VOCM2)") (class "Default")
      (node (ref "C24") (pin "1") (pinfunction "1_1") (pintype "passive"))
      (node (ref "U7") (pin "8") (pinfunction "8.VOCM2_8") (pintype "bidirectional"))
    )
    (net (code "76") (name "Net-(U7-10.VOUT2+)") (class "Default")
      (node (ref "R26") (pin "2") (pinfunction "2_2") (pintype "passive"))
      (node (ref "R30") (pin "1") (pinfunction "1_1") (pintype "passive"))
      (node (ref "U7") (pin "10") (pinfunction "10.VOUT2+_10") (pintype "output"))
    )
    (net (code "77") (name "Net-(U7-11.VOUT2-)") (class "Default")
      (node (ref "R24") (pin "2") (pinfunction "2_2") (pintype "passive"))
      (node (ref "R29") (pin "1") (pinfunction "1_1") (pintype "passive"))
      (node (ref "U7") (pin "11") (pinfunction "11.VOUT2-_11") (pintype "output"))
    )
    (net (code "78") (name "Net-(U7-14.VOUT1+)") (class "Default")
      (node (ref "R25") (pin "2") (pinfunction "2_2") (pintype "passive"))
      (node (ref "R28") (pin "1") (pinfunction "1_1") (pintype "passive"))
      (node (ref "U7") (pin "14") (pinfunction "14.VOUT1+_14") (pintype "output"))
    )
    (net (code "79") (name "Net-(U7-15.VOUT1-)") (class "Default")
      (node (ref "R23") (pin "2") (pinfunction "2_2") (pintype "passive"))
      (node (ref "R27") (pin "1") (pinfunction "1_1") (pintype "passive"))
      (node (ref "U7") (pin "15") (pinfunction "15.VOUT1-_15") (pintype "output"))
    )
    (net (code "80") (name "unconnected-(U1-ADC6-Pad19)") (class "Default")
      (node (ref "U1") (pin "19") (pinfunction "ADC6_19") (pintype "bidirectional"))
    )
    (net (code "81") (name "unconnected-(U1-ADC7-Pad22)") (class "Default")
      (node (ref "U1") (pin "22") (pinfunction "ADC7_22") (pintype "bidirectional"))
    )
    (net (code "82") (name "unconnected-(U1-AREF-Pad20)") (class "Default")
      (node (ref "U1") (pin "20") (pinfunction "AREF_20") (pintype "bidirectional"))
    )
    (net (code "83") (name "unconnected-(U1-PC2(ADC2)-Pad25)") (class "Default")
      (node (ref "U1") (pin "25") (pinfunction "PC2(ADC2)_25") (pintype "bidirectional"))
    )
    (net (code "84") (name "unconnected-(U1-PC4(ADC4{slash}SDA)-Pad27)") (class "Default")
      (node (ref "U1") (pin "27") (pinfunction "PC4(ADC4/SDA)_27") (pintype "bidirectional"))
    )
    (net (code "85") (name "unconnected-(U1-PC5(ADC5{slash}SCL)-Pad28)") (class "Default")
      (node (ref "U1") (pin "28") (pinfunction "PC5(ADC5/SCL)_28") (pintype "bidirectional"))
    )
    (net (code "86") (name "unconnected-(U4-AIC0-Pad3)") (class "Default")
      (node (ref "U4") (pin "3") (pinfunction "AIC0_3") (pintype "bidirectional"))
    )
    (net (code "87") (name "unconnected-(U4-GPIO5-Pad5)") (class "Default")
      (node (ref "U4") (pin "5") (pinfunction "GPIO5_5") (pintype "bidirectional"))
    )
    (net (code "88") (name "unconnected-(U4-GPIO6-Pad18)") (class "Default")
      (node (ref "U4") (pin "18") (pinfunction "GPIO6_18") (pintype "bidirectional"))
    )
    (net (code "89") (name "unconnected-(U4-GPIO10-Pad9)") (class "Default")
      (node (ref "U4") (pin "9") (pinfunction "GPIO10_9") (pintype "bidirectional"))
    )
    (net (code "90") (name "unconnected-(U4-GPIO11-Pad8)") (class "Default")
      (node (ref "U4") (pin "8") (pinfunction "GPIO11_8") (pintype "bidirectional"))
    )
    (net (code "91") (name "unconnected-(U4-GPIO12-Pad6)") (class "Default")
      (node (ref "U4") (pin "6") (pinfunction "GPIO12_6") (pintype "bidirectional"))
    )
    (net (code "92") (name "unconnected-(U4-GPIO13-Pad7)") (class "Default")
      (node (ref "U4") (pin "7") (pinfunction "GPIO13_7") (pintype "bidirectional"))
    )
    (net (code "93") (name "unconnected-(U4-PCM_CLK-Pad24)") (class "Default")
      (node (ref "U4") (pin "24") (pinfunction "PCM_CLK_24") (pintype "bidirectional"))
    )
    (net (code "94") (name "unconnected-(U4-PCM_IN-Pad21)") (class "Default")
      (node (ref "U4") (pin "21") (pinfunction "PCM_IN_21") (pintype "bidirectional"))
    )
    (net (code "95") (name "unconnected-(U4-PCM_OUT-Pad22)") (class "Default")
      (node (ref "U4") (pin "22") (pinfunction "PCM_OUT_22") (pintype "bidirectional"))
    )
    (net (code "96") (name "unconnected-(U4-PCM_SYNC-Pad23)") (class "Default")
      (node (ref "U4") (pin "23") (pinfunction "PCM_SYNC_23") (pintype "bidirectional"))
    )
    (net (code "97") (name "unconnected-(U4-SPI_CLK-Pad27)") (class "Default")
      (node (ref "U4") (pin "27") (pinfunction "SPI_CLK_27") (pintype "bidirectional"))
    )
    (net (code "98") (name "unconnected-(U4-SPI_MISO-Pad26)") (class "Default")
      (node (ref "U4") (pin "26") (pinfunction "SPI_MISO_26") (pintype "bidirectional"))
    )
    (net (code "99") (name "unconnected-(U4-SPI_MOSI-Pad28)") (class "Default")
      (node (ref "U4") (pin "28") (pinfunction "SPI_MOSI_28") (pintype "bidirectional"))
    )
    (net (code "100") (name "unconnected-(U4-SPI_SS-Pad25)") (class "Default")
      (node (ref "U4") (pin "25") (pinfunction "SPI_SS_25") (pintype "bidirectional"))
    )
    (net (code "101") (name "unconnected-(U4-USBD+-Pad12)") (class "Default")
      (node (ref "U4") (pin "12") (pinfunction "USBD+_12") (pintype "bidirectional"))
    )
    (net (code "102") (name "unconnected-(U4-USBD--Pad11)") (class "Default")
      (node (ref "U4") (pin "11") (pinfunction "USBD-_11") (pintype "bidirectional"))
    )
    (net (code "103") (name "unconnected-(U5-CTS-Pad11)") (class "Default")
      (node (ref "U5") (pin "11") (pinfunction "CTS_11") (pintype "input"))
    )
    (net (code "104") (name "unconnected-(U5-DCD-Pad10)") (class "Default")
      (node (ref "U5") (pin "10") (pinfunction "DCD_10") (pintype "input"))
    )
    (net (code "105") (name "unconnected-(U5-DSR-Pad9)") (class "Default")
      (node (ref "U5") (pin "9") (pinfunction "DSR_9") (pintype "input"))
    )
    (net (code "106") (name "unconnected-(U5-OSCI-Pad27)") (class "Default")
      (node (ref "U5") (pin "27") (pinfunction "OSCI_27") (pintype "input"))
    )
    (net (code "107") (name "unconnected-(U5-OSCO-Pad28)") (class "Default")
      (node (ref "U5") (pin "28") (pinfunction "OSCO_28") (pintype "output"))
    )
    (net (code "108") (name "unconnected-(U5-PWREN-Pad14)") (class "Default")
      (node (ref "U5") (pin "14") (pinfunction "PWREN_14") (pintype "input"))
    )
    (net (code "109") (name "unconnected-(U5-RESET-Pad19)") (class "Default")
      (node (ref "U5") (pin "19") (pinfunction "RESET_19") (pintype "input"))
    )
    (net (code "110") (name "unconnected-(U5-RI-Pad6)") (class "Default")
      (node (ref "U5") (pin "6") (pinfunction "RI_6") (pintype "input"))
    )
    (net (code "111") (name "unconnected-(U5-RTS-Pad3)") (class "Default")
      (node (ref "U5") (pin "3") (pinfunction "RTS_3") (pintype "output"))
    )
    (net (code "112") (name "unconnected-(U5-SLEEP-Pad12)") (class "Default")
      (node (ref "U5") (pin "12") (pinfunction "SLEEP_12") (pintype "input"))
    )
    (net (code "113") (name "unconnected-(U5-TXDEN-Pad13)") (class "Default")
      (node (ref "U5") (pin "13") (pinfunction "TXDEN_13") (pintype "input"))
    )
  )
)
